# scheme.net
KiCad netlist of a schematic drawn in EAGLE
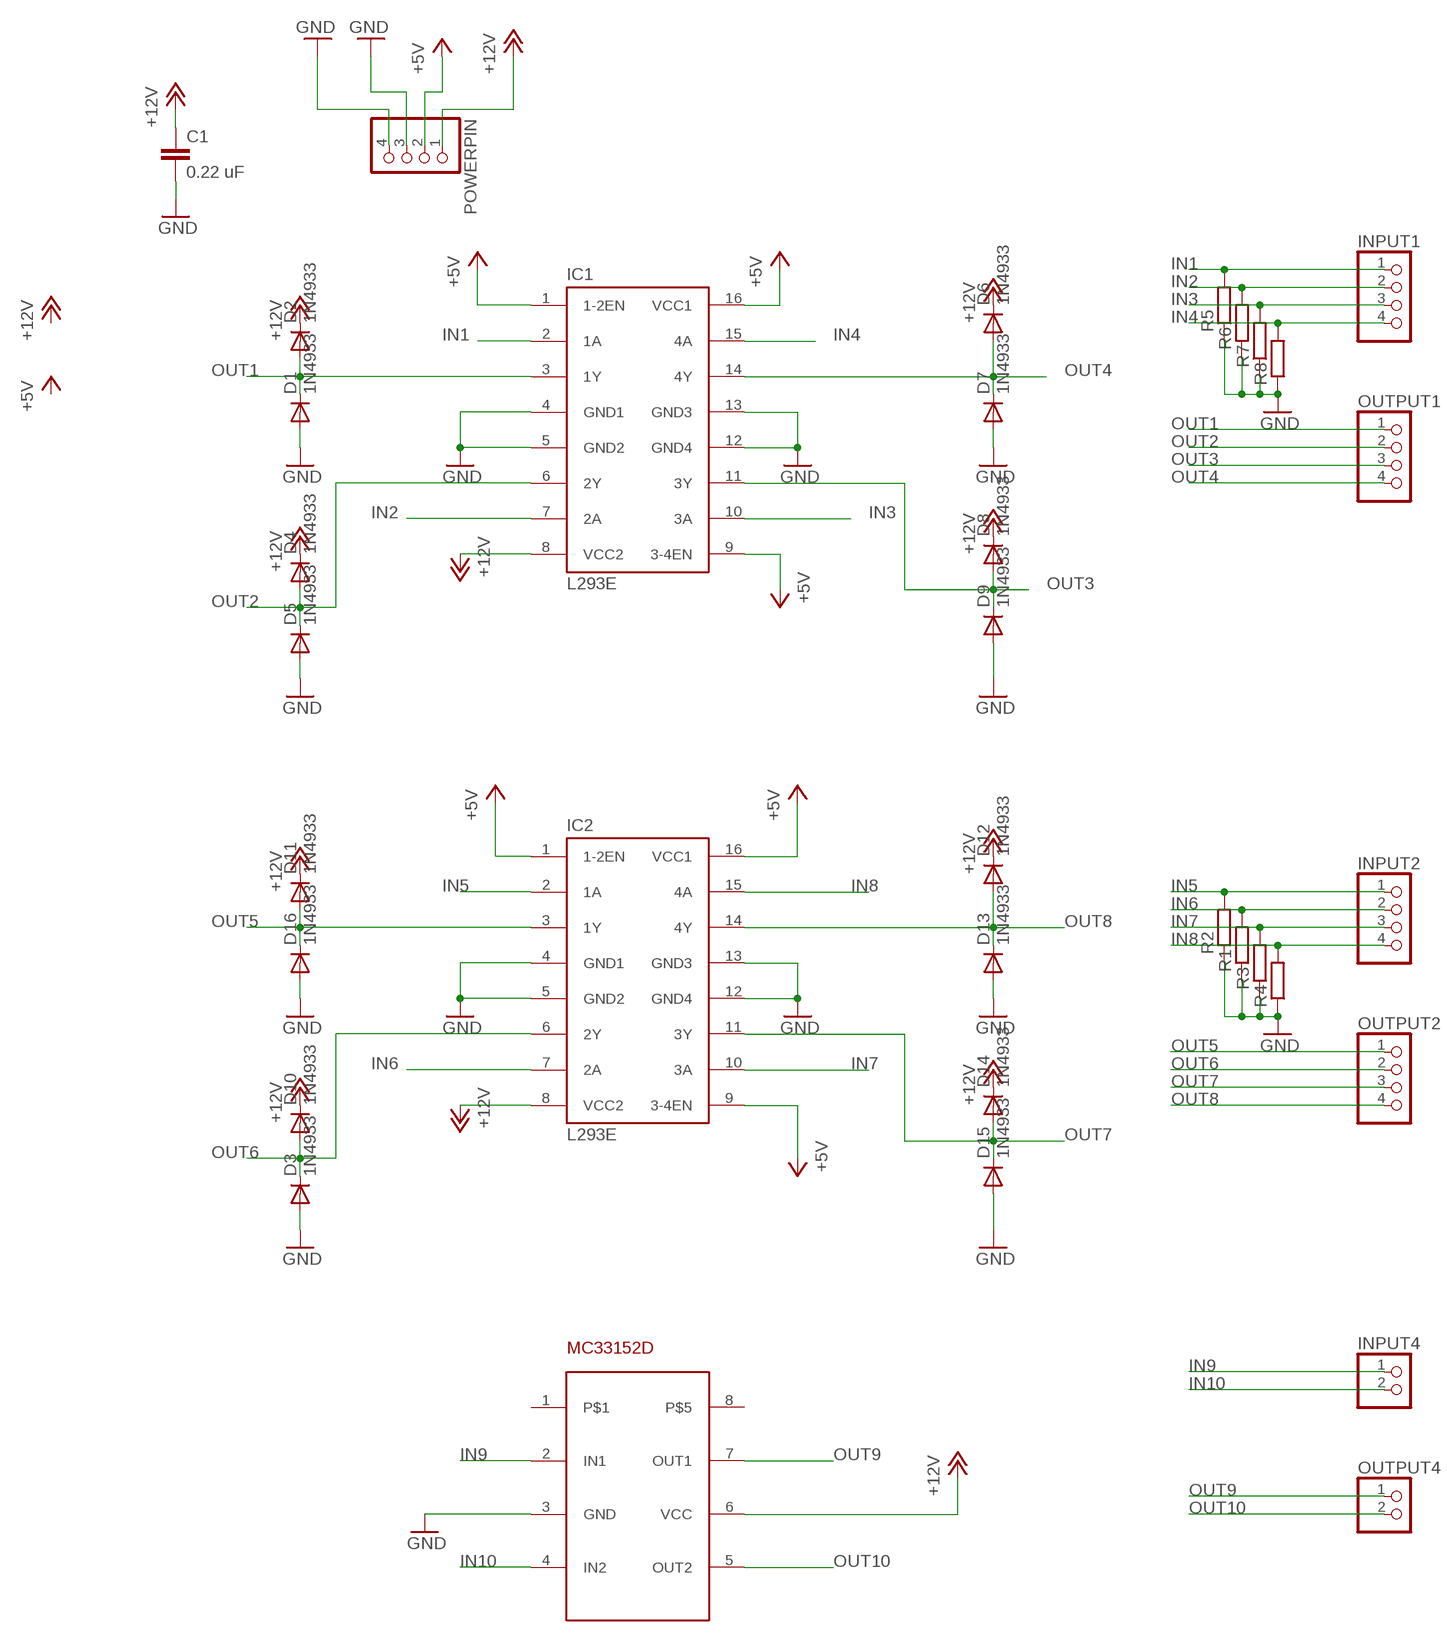
[diagram p0: schematic, sheet 1]

(export (version "E")
  (design (tool "Eeschema 10.0.6"))
  (components
    (comp (ref "C1")
      (value "0.22 uF")
      (footprint "eagle-import:C0805K")
      (libsource (lib "eagle-import") (part "C-EUC0805K"))
    )
    (comp (ref "D1")
      (value "1N4933")
      (footprint "eagle-import:DO41-10")
      (libsource (lib "eagle-import") (part "1N4933"))
    )
    (comp (ref "D2")
      (value "1N4933")
      (footprint "eagle-import:DO41-10")
      (libsource (lib "eagle-import") (part "1N4933"))
    )
    (comp (ref "D3")
      (value "1N4933")
      (footprint "eagle-import:DO41-10")
      (libsource (lib "eagle-import") (part "1N4933"))
    )
    (comp (ref "D4")
      (value "1N4933")
      (footprint "eagle-import:DO41-10")
      (libsource (lib "eagle-import") (part "1N4933"))
    )
    (comp (ref "D5")
      (value "1N4933")
      (footprint "eagle-import:DO41-10")
      (libsource (lib "eagle-import") (part "1N4933"))
    )
    (comp (ref "D6")
      (value "1N4933")
      (footprint "eagle-import:DO41-10")
      (libsource (lib "eagle-import") (part "1N4933"))
    )
    (comp (ref "D7")
      (value "1N4933")
      (footprint "eagle-import:DO41-10")
      (libsource (lib "eagle-import") (part "1N4933"))
    )
    (comp (ref "D8")
      (value "1N4933")
      (footprint "eagle-import:DO41-10")
      (libsource (lib "eagle-import") (part "1N4933"))
    )
    (comp (ref "D9")
      (value "1N4933")
      (footprint "eagle-import:DO41-10")
      (libsource (lib "eagle-import") (part "1N4933"))
    )
    (comp (ref "D10")
      (value "1N4933")
      (footprint "eagle-import:DO41-10")
      (libsource (lib "eagle-import") (part "1N4933"))
    )
    (comp (ref "D11")
      (value "1N4933")
      (footprint "eagle-import:DO41-10")
      (libsource (lib "eagle-import") (part "1N4933"))
    )
    (comp (ref "D12")
      (value "1N4933")
      (footprint "eagle-import:DO41-10")
      (libsource (lib "eagle-import") (part "1N4933"))
    )
    (comp (ref "D13")
      (value "1N4933")
      (footprint "eagle-import:DO41-10")
      (libsource (lib "eagle-import") (part "1N4933"))
    )
    (comp (ref "D14")
      (value "1N4933")
      (footprint "eagle-import:DO41-10")
      (libsource (lib "eagle-import") (part "1N4933"))
    )
    (comp (ref "D15")
      (value "1N4933")
      (footprint "eagle-import:DO41-10")
      (libsource (lib "eagle-import") (part "1N4933"))
    )
    (comp (ref "D16")
      (value "1N4933")
      (footprint "eagle-import:DO41-10")
      (libsource (lib "eagle-import") (part "1N4933"))
    )
    (comp (ref "IC1")
      (value "L293E")
      (footprint "eagle-import:DIL16")
      (fields (field (name "MF") "Arrow Electronics"))
      (libsource (lib "eagle-import") (part "L293E"))
    )
    (comp (ref "IC2")
      (value "L293E")
      (footprint "eagle-import:DIL16")
      (fields (field (name "MF") "Arrow Electronics"))
      (libsource (lib "eagle-import") (part "L293E"))
    )
    (comp (ref "INPUT1")
      (value "PINHD-1X4")
      (footprint "eagle-import:1X04")
      (libsource (lib "eagle-import") (part "PINHD-1X4"))
    )
    (comp (ref "INPUT2")
      (value "PINHD-1X4")
      (footprint "eagle-import:1X04")
      (libsource (lib "eagle-import") (part "PINHD-1X4"))
    )
    (comp (ref "INPUT4")
      (value "PINHD-1X2")
      (footprint "eagle-import:1X02")
      (libsource (lib "eagle-import") (part "PINHD-1X2"))
    )
    (comp (ref "MC33152D")
      (value "MC33152D")
      (footprint "eagle-import:SOIC8")
      (libsource (lib "eagle-import") (part "MC33152D"))
    )
    (comp (ref "OUTPUT1")
      (value "PINHD-1X4")
      (footprint "eagle-import:1X04")
      (libsource (lib "eagle-import") (part "PINHD-1X4"))
    )
    (comp (ref "OUTPUT2")
      (value "PINHD-1X4")
      (footprint "eagle-import:1X04")
      (libsource (lib "eagle-import") (part "PINHD-1X4"))
    )
    (comp (ref "OUTPUT4")
      (value "PINHD-1X2")
      (footprint "eagle-import:1X02")
      (libsource (lib "eagle-import") (part "PINHD-1X2"))
    )
    (comp (ref "POWERPIN")
      (value "PINHD-1X4")
      (footprint "eagle-import:1X04")
      (libsource (lib "eagle-import") (part "PINHD-1X4"))
    )
    (comp (ref "R1")
      (value "R-EU_R0805")
      (footprint "eagle-import:R0805")
      (libsource (lib "eagle-import") (part "R-EU_R0805"))
    )
    (comp (ref "R2")
      (value "R-EU_R0805")
      (footprint "eagle-import:R0805")
      (libsource (lib "eagle-import") (part "R-EU_R0805"))
    )
    (comp (ref "R3")
      (value "R-EU_R0805")
      (footprint "eagle-import:R0805")
      (libsource (lib "eagle-import") (part "R-EU_R0805"))
    )
    (comp (ref "R4")
      (value "R-EU_R0805")
      (footprint "eagle-import:R0805")
      (libsource (lib "eagle-import") (part "R-EU_R0805"))
    )
    (comp (ref "R5")
      (value "R-EU_R0805")
      (footprint "eagle-import:R0805")
      (libsource (lib "eagle-import") (part "R-EU_R0805"))
    )
    (comp (ref "R6")
      (value "R-EU_R0805")
      (footprint "eagle-import:R0805")
      (libsource (lib "eagle-import") (part "R-EU_R0805"))
    )
    (comp (ref "R7")
      (value "R-EU_R0805")
      (footprint "eagle-import:R0805")
      (libsource (lib "eagle-import") (part "R-EU_R0805"))
    )
    (comp (ref "R8")
      (value "R-EU_R0805")
      (footprint "eagle-import:R0805")
      (libsource (lib "eagle-import") (part "R-EU_R0805"))
    )
  )
  (nets
    (net (code "1") (name "+5V") (class "Default")
      (node (ref "IC1") (pin "1") (pinfunction "1-2EN_1") (pintype "input"))
      (node (ref "IC1") (pin "16") (pinfunction "VCC1_16") (pintype "power_in"))
      (node (ref "IC1") (pin "9") (pinfunction "3-4EN_9") (pintype "input"))
      (node (ref "IC2") (pin "1") (pinfunction "1-2EN_1") (pintype "input"))
      (node (ref "IC2") (pin "16") (pinfunction "VCC1_16") (pintype "power_in"))
      (node (ref "IC2") (pin "9") (pinfunction "3-4EN_9") (pintype "input"))
      (node (ref "POWERPIN") (pin "2") (pinfunction "2_2") (pintype "passive"))
    )
    (net (code "2") (name "+12V") (class "Default")
      (node (ref "C1") (pin "1") (pinfunction "1_1") (pintype "passive"))
      (node (ref "D10") (pin "C") (pinfunction "C_C") (pintype "passive"))
      (node (ref "D11") (pin "C") (pinfunction "C_C") (pintype "passive"))
      (node (ref "D12") (pin "C") (pinfunction "C_C") (pintype "passive"))
      (node (ref "D14") (pin "C") (pinfunction "C_C") (pintype "passive"))
      (node (ref "D2") (pin "C") (pinfunction "C_C") (pintype "passive"))
      (node (ref "D4") (pin "C") (pinfunction "C_C") (pintype "passive"))
      (node (ref "D6") (pin "C") (pinfunction "C_C") (pintype "passive"))
      (node (ref "D8") (pin "C") (pinfunction "C_C") (pintype "passive"))
      (node (ref "IC1") (pin "8") (pinfunction "VCC2_8") (pintype "power_in"))
      (node (ref "IC2") (pin "8") (pinfunction "VCC2_8") (pintype "power_in"))
      (node (ref "MC33152D") (pin "6") (pinfunction "VCC_6") (pintype "power_in"))
      (node (ref "POWERPIN") (pin "1") (pinfunction "1_1") (pintype "passive"))
    )
    (net (code "3") (name "/IN1") (class "Default")
      (node (ref "IC1") (pin "2") (pinfunction "1A_2") (pintype "input"))
      (node (ref "INPUT1") (pin "1") (pinfunction "1_1") (pintype "passive"))
      (node (ref "R5") (pin "2") (pinfunction "2_2") (pintype "passive"))
    )
    (net (code "4") (name "/IN2") (class "Default")
      (node (ref "IC1") (pin "7") (pinfunction "2A_7") (pintype "input"))
      (node (ref "INPUT1") (pin "2") (pinfunction "2_2") (pintype "passive"))
      (node (ref "R6") (pin "2") (pinfunction "2_2") (pintype "passive"))
    )
    (net (code "5") (name "/IN3") (class "Default")
      (node (ref "IC1") (pin "10") (pinfunction "3A_10") (pintype "input"))
      (node (ref "INPUT1") (pin "3") (pinfunction "3_3") (pintype "passive"))
      (node (ref "R7") (pin "2") (pinfunction "2_2") (pintype "passive"))
    )
    (net (code "6") (name "/IN4") (class "Default")
      (node (ref "IC1") (pin "15") (pinfunction "4A_15") (pintype "input"))
      (node (ref "INPUT1") (pin "4") (pinfunction "4_4") (pintype "passive"))
      (node (ref "R8") (pin "2") (pinfunction "2_2") (pintype "passive"))
    )
    (net (code "7") (name "/IN5") (class "Default")
      (node (ref "IC2") (pin "2") (pinfunction "1A_2") (pintype "input"))
      (node (ref "INPUT2") (pin "1") (pinfunction "1_1") (pintype "passive"))
      (node (ref "R2") (pin "2") (pinfunction "2_2") (pintype "passive"))
    )
    (net (code "8") (name "/IN6") (class "Default")
      (node (ref "IC2") (pin "7") (pinfunction "2A_7") (pintype "input"))
      (node (ref "INPUT2") (pin "2") (pinfunction "2_2") (pintype "passive"))
      (node (ref "R1") (pin "2") (pinfunction "2_2") (pintype "passive"))
    )
    (net (code "9") (name "/IN7") (class "Default")
      (node (ref "IC2") (pin "10") (pinfunction "3A_10") (pintype "input"))
      (node (ref "INPUT2") (pin "3") (pinfunction "3_3") (pintype "passive"))
      (node (ref "R3") (pin "2") (pinfunction "2_2") (pintype "passive"))
    )
    (net (code "10") (name "/IN8") (class "Default")
      (node (ref "IC2") (pin "15") (pinfunction "4A_15") (pintype "input"))
      (node (ref "INPUT2") (pin "4") (pinfunction "4_4") (pintype "passive"))
      (node (ref "R4") (pin "2") (pinfunction "2_2") (pintype "passive"))
    )
    (net (code "11") (name "/IN9") (class "Default")
      (node (ref "INPUT4") (pin "1") (pinfunction "1_1") (pintype "passive"))
      (node (ref "MC33152D") (pin "2") (pinfunction "IN1_2") (pintype "input"))
    )
    (net (code "12") (name "/IN10") (class "Default")
      (node (ref "INPUT4") (pin "2") (pinfunction "2_2") (pintype "passive"))
      (node (ref "MC33152D") (pin "4") (pinfunction "IN2_4") (pintype "input"))
    )
    (net (code "13") (name "/OUT1") (class "Default")
      (node (ref "D1") (pin "C") (pinfunction "C_C") (pintype "passive"))
      (node (ref "D2") (pin "A") (pinfunction "A_A") (pintype "passive"))
      (node (ref "IC1") (pin "3") (pinfunction "1Y_3") (pintype "output"))
      (node (ref "OUTPUT1") (pin "1") (pinfunction "1_1") (pintype "passive"))
    )
    (net (code "14") (name "/OUT2") (class "Default")
      (node (ref "D4") (pin "A") (pinfunction "A_A") (pintype "passive"))
      (node (ref "D5") (pin "C") (pinfunction "C_C") (pintype "passive"))
      (node (ref "IC1") (pin "6") (pinfunction "2Y_6") (pintype "output"))
      (node (ref "OUTPUT1") (pin "2") (pinfunction "2_2") (pintype "passive"))
    )
    (net (code "15") (name "/OUT3") (class "Default")
      (node (ref "D8") (pin "A") (pinfunction "A_A") (pintype "passive"))
      (node (ref "D9") (pin "C") (pinfunction "C_C") (pintype "passive"))
      (node (ref "IC1") (pin "11") (pinfunction "3Y_11") (pintype "output"))
      (node (ref "OUTPUT1") (pin "3") (pinfunction "3_3") (pintype "passive"))
    )
    (net (code "16") (name "/OUT4") (class "Default")
      (node (ref "D6") (pin "A") (pinfunction "A_A") (pintype "passive"))
      (node (ref "D7") (pin "C") (pinfunction "C_C") (pintype "passive"))
      (node (ref "IC1") (pin "14") (pinfunction "4Y_14") (pintype "output"))
      (node (ref "OUTPUT1") (pin "4") (pinfunction "4_4") (pintype "passive"))
    )
    (net (code "17") (name "/OUT5") (class "Default")
      (node (ref "D11") (pin "A") (pinfunction "A_A") (pintype "passive"))
      (node (ref "D16") (pin "C") (pinfunction "C_C") (pintype "passive"))
      (node (ref "IC2") (pin "3") (pinfunction "1Y_3") (pintype "output"))
      (node (ref "OUTPUT2") (pin "1") (pinfunction "1_1") (pintype "passive"))
    )
    (net (code "18") (name "/OUT6") (class "Default")
      (node (ref "D10") (pin "A") (pinfunction "A_A") (pintype "passive"))
      (node (ref "D3") (pin "C") (pinfunction "C_C") (pintype "passive"))
      (node (ref "IC2") (pin "6") (pinfunction "2Y_6") (pintype "output"))
      (node (ref "OUTPUT2") (pin "2") (pinfunction "2_2") (pintype "passive"))
    )
    (net (code "19") (name "/OUT7") (class "Default")
      (node (ref "D14") (pin "A") (pinfunction "A_A") (pintype "passive"))
      (node (ref "D15") (pin "C") (pinfunction "C_C") (pintype "passive"))
      (node (ref "IC2") (pin "11") (pinfunction "3Y_11") (pintype "output"))
      (node (ref "OUTPUT2") (pin "3") (pinfunction "3_3") (pintype "passive"))
    )
    (net (code "20") (name "/OUT8") (class "Default")
      (node (ref "D12") (pin "A") (pinfunction "A_A") (pintype "passive"))
      (node (ref "D13") (pin "C") (pinfunction "C_C") (pintype "passive"))
      (node (ref "IC2") (pin "14") (pinfunction "4Y_14") (pintype "output"))
      (node (ref "OUTPUT2") (pin "4") (pinfunction "4_4") (pintype "passive"))
    )
    (net (code "21") (name "/OUT9") (class "Default")
      (node (ref "MC33152D") (pin "7") (pinfunction "OUT1_7") (pintype "output"))
      (node (ref "OUTPUT4") (pin "1") (pinfunction "1_1") (pintype "passive"))
    )
    (net (code "22") (name "/OUT10") (class "Default")
      (node (ref "MC33152D") (pin "5") (pinfunction "OUT2_5") (pintype "output"))
      (node (ref "OUTPUT4") (pin "2") (pinfunction "2_2") (pintype "passive"))
    )
    (net (code "23") (name "GND") (class "Default")
      (node (ref "C1") (pin "2") (pinfunction "2_2") (pintype "passive"))
      (node (ref "D1") (pin "A") (pinfunction "A_A") (pintype "passive"))
      (node (ref "D13") (pin "A") (pinfunction "A_A") (pintype "passive"))
      (node (ref "D15") (pin "A") (pinfunction "A_A") (pintype "passive"))
      (node (ref "D16") (pin "A") (pinfunction "A_A") (pintype "passive"))
      (node (ref "D3") (pin "A") (pinfunction "A_A") (pintype "passive"))
      (node (ref "D5") (pin "A") (pinfunction "A_A") (pintype "passive"))
      (node (ref "D7") (pin "A") (pinfunction "A_A") (pintype "passive"))
      (node (ref "D9") (pin "A") (pinfunction "A_A") (pintype "passive"))
      (node (ref "IC1") (pin "12") (pinfunction "GND4_12") (pintype "power_in"))
      (node (ref "IC1") (pin "13") (pinfunction "GND3_13") (pintype "power_in"))
      (node (ref "IC1") (pin "4") (pinfunction "GND1_4") (pintype "power_in"))
      (node (ref "IC1") (pin "5") (pinfunction "GND2_5") (pintype "power_in"))
      (node (ref "IC2") (pin "12") (pinfunction "GND4_12") (pintype "power_in"))
      (node (ref "IC2") (pin "13") (pinfunction "GND3_13") (pintype "power_in"))
      (node (ref "IC2") (pin "4") (pinfunction "GND1_4") (pintype "power_in"))
      (node (ref "IC2") (pin "5") (pinfunction "GND2_5") (pintype "power_in"))
      (node (ref "MC33152D") (pin "3") (pinfunction "GND_3") (pintype "power_in"))
      (node (ref "POWERPIN") (pin "3") (pinfunction "3_3") (pintype "passive"))
      (node (ref "POWERPIN") (pin "4") (pinfunction "4_4") (pintype "passive"))
      (node (ref "R1") (pin "1") (pinfunction "1_1") (pintype "passive"))
      (node (ref "R2") (pin "1") (pinfunction "1_1") (pintype "passive"))
      (node (ref "R3") (pin "1") (pinfunction "1_1") (pintype "passive"))
      (node (ref "R4") (pin "1") (pinfunction "1_1") (pintype "passive"))
      (node (ref "R5") (pin "1") (pinfunction "1_1") (pintype "passive"))
      (node (ref "R6") (pin "1") (pinfunction "1_1") (pintype "passive"))
      (node (ref "R7") (pin "1") (pinfunction "1_1") (pintype "passive"))
      (node (ref "R8") (pin "1") (pinfunction "1_1") (pintype "passive"))
    )
    (net (code "24") (name "unconnected-(MC33152D-P$1-Pad1)") (class "Default")
      (node (ref "MC33152D") (pin "1") (pinfunction "P$1_1") (pintype "no_connect"))
    )
    (net (code "25") (name "unconnected-(MC33152D-P$5-Pad8)") (class "Default")
      (node (ref "MC33152D") (pin "8") (pinfunction "P$5_8") (pintype "no_connect"))
    )
  )
)
